# sensors.net
KiCad netlist of a schematic drawn in Altium Designer
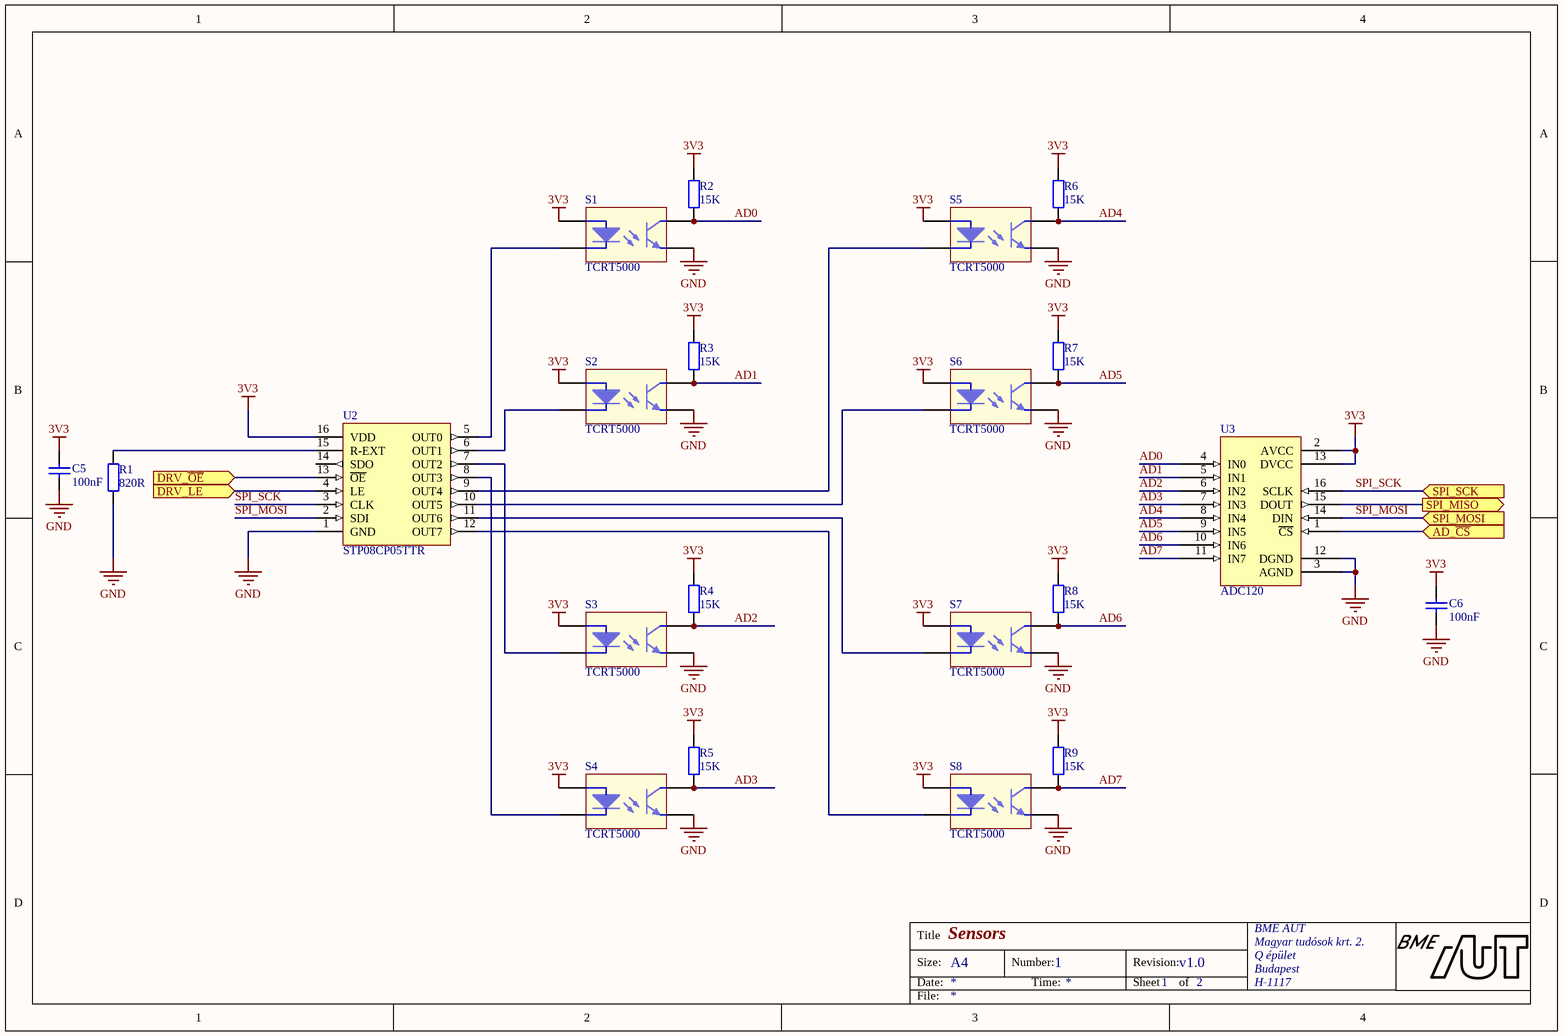
[diagram p0: sensors.SchDoc]

(export (version "E")
  (design (tool "Eeschema 10.0.6"))
  (components
    (comp (ref "C5")
      (value "100nF")
      (footprint "FP_0805_CAP_085")
      (description "Capacitor")
      (libsource (lib "hallglib") (part "CAP"))
    )
    (comp (ref "C6")
      (value "100nF")
      (footprint "FP_0805_CAP_085")
      (description "Capacitor")
      (libsource (lib "hallglib") (part "CAP"))
    )
    (comp (ref "R1")
      (value "820R")
      (footprint "FP_0805_RES")
      (description "Resistor")
      (libsource (lib "hallglib") (part "RES"))
    )
    (comp (ref "R2")
      (value "15K")
      (footprint "FP_0805_RES")
      (description "Resistor")
      (libsource (lib "hallglib") (part "RES"))
    )
    (comp (ref "R3")
      (value "15K")
      (footprint "FP_0805_RES")
      (description "Resistor")
      (libsource (lib "hallglib") (part "RES"))
    )
    (comp (ref "R4")
      (value "15K")
      (footprint "FP_0805_RES")
      (description "Resistor")
      (libsource (lib "hallglib") (part "RES"))
    )
    (comp (ref "R5")
      (value "15K")
      (footprint "FP_0805_RES")
      (description "Resistor")
      (libsource (lib "hallglib") (part "RES"))
    )
    (comp (ref "R6")
      (value "15K")
      (footprint "FP_0805_RES")
      (description "Resistor")
      (libsource (lib "hallglib") (part "RES"))
    )
    (comp (ref "R7")
      (value "15K")
      (footprint "FP_0805_RES")
      (description "Resistor")
      (libsource (lib "hallglib") (part "RES"))
    )
    (comp (ref "R8")
      (value "15K")
      (footprint "FP_0805_RES")
      (description "Resistor")
      (libsource (lib "hallglib") (part "RES"))
    )
    (comp (ref "R9")
      (value "15K")
      (footprint "FP_0805_RES")
      (description "Resistor")
      (libsource (lib "hallglib") (part "RES"))
    )
    (comp (ref "S1")
      (value "TCRT5000")
      (footprint "TCRT5000")
      (description "Reflective Optical Sensor")
      (libsource (lib "hallglib") (part "TCRT5000"))
    )
    (comp (ref "S2")
      (value "TCRT5000")
      (footprint "TCRT5000")
      (description "Reflective Optical Sensor")
      (libsource (lib "hallglib") (part "TCRT5000"))
    )
    (comp (ref "S3")
      (value "TCRT5000")
      (footprint "TCRT5000")
      (description "Reflective Optical Sensor")
      (libsource (lib "hallglib") (part "TCRT5000"))
    )
    (comp (ref "S4")
      (value "TCRT5000")
      (footprint "TCRT5000")
      (description "Reflective Optical Sensor")
      (libsource (lib "hallglib") (part "TCRT5000"))
    )
    (comp (ref "S5")
      (value "TCRT5000")
      (footprint "TCRT5000")
      (description "Reflective Optical Sensor")
      (libsource (lib "hallglib") (part "TCRT5000"))
    )
    (comp (ref "S6")
      (value "TCRT5000")
      (footprint "TCRT5000")
      (description "Reflective Optical Sensor")
      (libsource (lib "hallglib") (part "TCRT5000"))
    )
    (comp (ref "S7")
      (value "TCRT5000")
      (footprint "TCRT5000")
      (description "Reflective Optical Sensor")
      (libsource (lib "hallglib") (part "TCRT5000"))
    )
    (comp (ref "S8")
      (value "TCRT5000")
      (footprint "TCRT5000")
      (description "Reflective Optical Sensor")
      (libsource (lib "hallglib") (part "TCRT5000"))
    )
    (comp (ref "U2")
      (value "STP08CP05TTR")
      (footprint "TSOP65P640X120-16M")
      (description "Low voltage, low current power 8-bit shift register")
      (libsource (lib "hallglib") (part "STP08CP05TTR"))
    )
    (comp (ref "U3")
      (value "ADC120")
      (footprint "TSOP65P640X120-16N")
      (libsource (lib "hallglib") (part "ADC120"))
    )
  )
  (nets
    (net (code "1") (name "/AD0") (class "Default")
      (node (ref "R2") (pin "1") (pinfunction "1_1") (pintype "passive"))
      (node (ref "S1") (pin "3") (pinfunction "C_3") (pintype "passive"))
      (node (ref "U3") (pin "4") (pinfunction "IN0_4") (pintype "input"))
    )
    (net (code "2") (name "/AD1") (class "Default")
      (node (ref "R3") (pin "1") (pinfunction "1_1") (pintype "passive"))
      (node (ref "S2") (pin "3") (pinfunction "C_3") (pintype "passive"))
      (node (ref "U3") (pin "5") (pinfunction "IN1_5") (pintype "input"))
    )
    (net (code "3") (name "/AD2") (class "Default")
      (node (ref "R4") (pin "1") (pinfunction "1_1") (pintype "passive"))
      (node (ref "S3") (pin "3") (pinfunction "C_3") (pintype "passive"))
      (node (ref "U3") (pin "6") (pinfunction "IN2_6") (pintype "input"))
    )
    (net (code "4") (name "/AD3") (class "Default")
      (node (ref "R5") (pin "1") (pinfunction "1_1") (pintype "passive"))
      (node (ref "S4") (pin "3") (pinfunction "C_3") (pintype "passive"))
      (node (ref "U3") (pin "7") (pinfunction "IN3_7") (pintype "input"))
    )
    (net (code "5") (name "/AD4") (class "Default")
      (node (ref "R6") (pin "1") (pinfunction "1_1") (pintype "passive"))
      (node (ref "S5") (pin "3") (pinfunction "C_3") (pintype "passive"))
      (node (ref "U3") (pin "8") (pinfunction "IN4_8") (pintype "input"))
    )
    (net (code "6") (name "/AD5") (class "Default")
      (node (ref "R7") (pin "1") (pinfunction "1_1") (pintype "passive"))
      (node (ref "S6") (pin "3") (pinfunction "C_3") (pintype "passive"))
      (node (ref "U3") (pin "9") (pinfunction "IN5_9") (pintype "input"))
    )
    (net (code "7") (name "/AD6") (class "Default")
      (node (ref "R8") (pin "1") (pinfunction "1_1") (pintype "passive"))
      (node (ref "S7") (pin "3") (pinfunction "C_3") (pintype "passive"))
      (node (ref "U3") (pin "10") (pinfunction "IN6_10") (pintype "input"))
    )
    (net (code "8") (name "/AD7") (class "Default")
      (node (ref "R9") (pin "1") (pinfunction "1_1") (pintype "passive"))
      (node (ref "S8") (pin "3") (pinfunction "C_3") (pintype "passive"))
      (node (ref "U3") (pin "11") (pinfunction "IN7_11") (pintype "input"))
    )
    (net (code "9") (name "/AD_~{CS}") (class "Default")
      (node (ref "U3") (pin "1") (pinfunction "~{CS}_1") (pintype "input"))
    )
    (net (code "10") (name "/DRV_LE") (class "Default")
      (node (ref "U2") (pin "4") (pinfunction "LE_4") (pintype "input"))
    )
    (net (code "11") (name "/DRV_~{OE}") (class "Default")
      (node (ref "U2") (pin "13") (pinfunction "~{OE}_13") (pintype "input"))
    )
    (net (code "12") (name "/SPI_MISO") (class "Default")
      (node (ref "U3") (pin "15") (pinfunction "DOUT_15") (pintype "output"))
    )
    (net (code "13") (name "/SPI_MOSI") (class "Default")
      (node (ref "U2") (pin "2") (pinfunction "SDI_2") (pintype "input"))
      (node (ref "U3") (pin "14") (pinfunction "DIN_14") (pintype "input"))
    )
    (net (code "14") (name "/SPI_SCK") (class "Default")
      (node (ref "U2") (pin "3") (pinfunction "CLK_3") (pintype "input"))
      (node (ref "U3") (pin "16") (pinfunction "SCLK_16") (pintype "input"))
    )
    (net (code "15") (name "3V3") (class "Default")
      (node (ref "C5") (pin "2") (pinfunction "2_2") (pintype "passive"))
      (node (ref "C6") (pin "2") (pinfunction "2_2") (pintype "passive"))
      (node (ref "R2") (pin "2") (pinfunction "2_2") (pintype "passive"))
      (node (ref "R3") (pin "2") (pinfunction "2_2") (pintype "passive"))
      (node (ref "R4") (pin "2") (pinfunction "2_2") (pintype "passive"))
      (node (ref "R5") (pin "2") (pinfunction "2_2") (pintype "passive"))
      (node (ref "R6") (pin "2") (pinfunction "2_2") (pintype "passive"))
      (node (ref "R7") (pin "2") (pinfunction "2_2") (pintype "passive"))
      (node (ref "R8") (pin "2") (pinfunction "2_2") (pintype "passive"))
      (node (ref "R9") (pin "2") (pinfunction "2_2") (pintype "passive"))
      (node (ref "S1") (pin "1") (pinfunction "A_1") (pintype "passive"))
      (node (ref "S2") (pin "1") (pinfunction "A_1") (pintype "passive"))
      (node (ref "S3") (pin "1") (pinfunction "A_1") (pintype "passive"))
      (node (ref "S4") (pin "1") (pinfunction "A_1") (pintype "passive"))
      (node (ref "S5") (pin "1") (pinfunction "A_1") (pintype "passive"))
      (node (ref "S6") (pin "1") (pinfunction "A_1") (pintype "passive"))
      (node (ref "S7") (pin "1") (pinfunction "A_1") (pintype "passive"))
      (node (ref "S8") (pin "1") (pinfunction "A_1") (pintype "passive"))
      (node (ref "U2") (pin "16") (pinfunction "VDD_16") (pintype "power_in"))
      (node (ref "U3") (pin "13") (pinfunction "DVCC_13") (pintype "power_in"))
      (node (ref "U3") (pin "2") (pinfunction "AVCC_2") (pintype "power_in"))
    )
    (net (code "16") (name "GND") (class "Default")
      (node (ref "C5") (pin "1") (pinfunction "1_1") (pintype "passive"))
      (node (ref "C6") (pin "1") (pinfunction "1_1") (pintype "passive"))
      (node (ref "R1") (pin "1") (pinfunction "1_1") (pintype "passive"))
      (node (ref "S1") (pin "4") (pinfunction "E_4") (pintype "passive"))
      (node (ref "S2") (pin "4") (pinfunction "E_4") (pintype "passive"))
      (node (ref "S3") (pin "4") (pinfunction "E_4") (pintype "passive"))
      (node (ref "S4") (pin "4") (pinfunction "E_4") (pintype "passive"))
      (node (ref "S5") (pin "4") (pinfunction "E_4") (pintype "passive"))
      (node (ref "S6") (pin "4") (pinfunction "E_4") (pintype "passive"))
      (node (ref "S7") (pin "4") (pinfunction "E_4") (pintype "passive"))
      (node (ref "S8") (pin "4") (pinfunction "E_4") (pintype "passive"))
      (node (ref "U2") (pin "1") (pinfunction "GND_1") (pintype "passive"))
      (node (ref "U3") (pin "12") (pinfunction "DGND_12") (pintype "power_in"))
      (node (ref "U3") (pin "3") (pinfunction "AGND_3") (pintype "power_in"))
    )
    (net (code "17") (name "Net-(S1-K)") (class "Default")
      (node (ref "S1") (pin "2") (pinfunction "K_2") (pintype "passive"))
      (node (ref "U2") (pin "5") (pinfunction "OUT0_5") (pintype "output"))
    )
    (net (code "18") (name "Net-(S2-K)") (class "Default")
      (node (ref "S2") (pin "2") (pinfunction "K_2") (pintype "passive"))
      (node (ref "U2") (pin "6") (pinfunction "OUT1_6") (pintype "output"))
    )
    (net (code "19") (name "Net-(S3-K)") (class "Default")
      (node (ref "S3") (pin "2") (pinfunction "K_2") (pintype "passive"))
      (node (ref "U2") (pin "7") (pinfunction "OUT2_7") (pintype "output"))
    )
    (net (code "20") (name "Net-(S4-K)") (class "Default")
      (node (ref "S4") (pin "2") (pinfunction "K_2") (pintype "passive"))
      (node (ref "U2") (pin "8") (pinfunction "OUT3_8") (pintype "output"))
    )
    (net (code "21") (name "Net-(S5-K)") (class "Default")
      (node (ref "S5") (pin "2") (pinfunction "K_2") (pintype "passive"))
      (node (ref "U2") (pin "9") (pinfunction "OUT4_9") (pintype "output"))
    )
    (net (code "22") (name "Net-(S6-K)") (class "Default")
      (node (ref "S6") (pin "2") (pinfunction "K_2") (pintype "passive"))
      (node (ref "U2") (pin "10") (pinfunction "OUT5_10") (pintype "output"))
    )
    (net (code "23") (name "Net-(S7-K)") (class "Default")
      (node (ref "S7") (pin "2") (pinfunction "K_2") (pintype "passive"))
      (node (ref "U2") (pin "11") (pinfunction "OUT6_11") (pintype "output"))
    )
    (net (code "24") (name "Net-(S8-K)") (class "Default")
      (node (ref "S8") (pin "2") (pinfunction "K_2") (pintype "passive"))
      (node (ref "U2") (pin "12") (pinfunction "OUT7_12") (pintype "output"))
    )
    (net (code "25") (name "Net-(U2-R-EXT)") (class "Default")
      (node (ref "R1") (pin "2") (pinfunction "2_2") (pintype "passive"))
      (node (ref "U2") (pin "15") (pinfunction "R-EXT_15") (pintype "passive"))
    )
    (net (code "26") (name "unconnected-(U2-SDO-Pad14)") (class "Default")
      (node (ref "U2") (pin "14") (pinfunction "SDO_14") (pintype "output"))
    )
  )
)
